# PowerandConnectors_2.net
KiCad netlist of a schematic drawn in Altium Designer
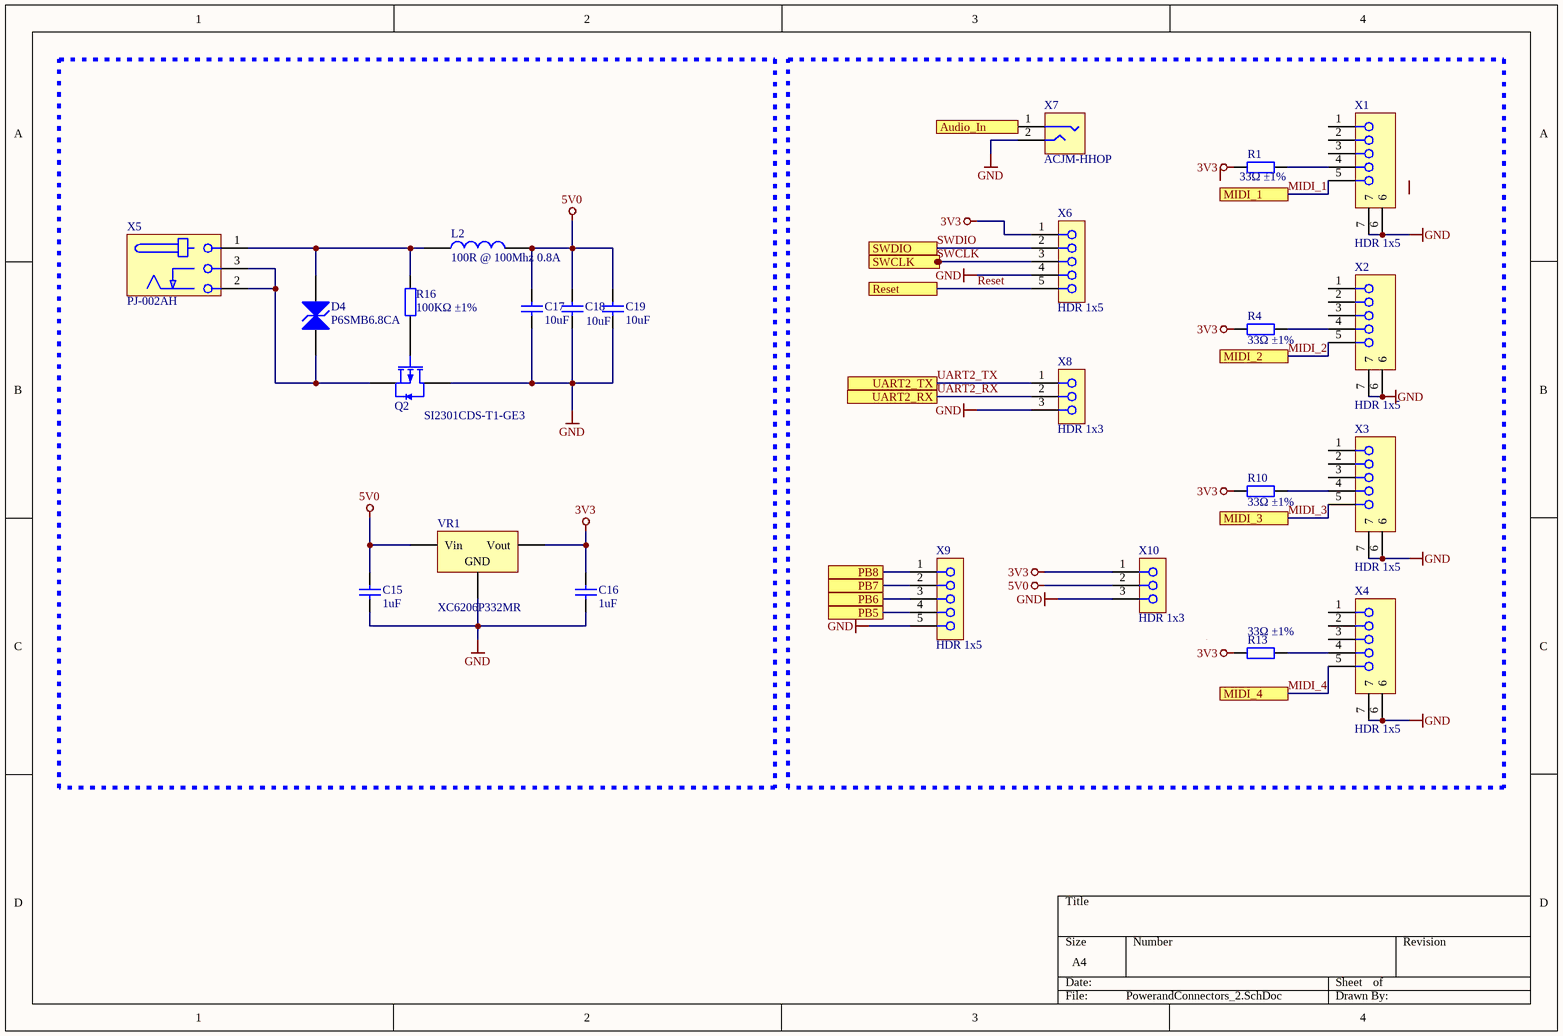
[diagram p0: PowerandConnectors_2.SchDoc]

(export (version "E")
  (design (tool "Eeschema 10.0.6"))
  (components
    (comp (ref "C15")
      (value "1uF")
      (footprint "0603_C")
      (description "Chip capacitors")
      (fields
        (field (name "MANUFACTURER") "Samsung Electro-Mechanics")
        (field (name "PARTNUMBER") "CL10A105KB8NNNC")
      )
      (libsource (lib "Cap") (part "0603 1uF (105) 10% 50V"))
    )
    (comp (ref "C16")
      (value "1uF")
      (footprint "0603_C")
      (description "Chip capacitors")
      (fields
        (field (name "MANUFACTURER") "Samsung Electro-Mechanics")
        (field (name "PARTNUMBER") "CL10A105KB8NNNC")
      )
      (libsource (lib "Cap") (part "0603 1uF (105) 10% 50V"))
    )
    (comp (ref "C17")
      (value "10uF")
      (footprint "0805_C")
      (description "Chip capacitors")
      (fields
        (field (name "MANUFACTURER") "Samsung Electro-Mechanics")
        (field (name "PARTNUMBER") "CL21A106KAYNNNE")
      )
      (libsource (lib "Cap") (part "0805 10uF (106) 10% 25V"))
    )
    (comp (ref "C18")
      (value "10uF")
      (footprint "0805_C")
      (description "Chip capacitors")
      (fields
        (field (name "MANUFACTURER") "Samsung Electro-Mechanics")
        (field (name "PARTNUMBER") "CL21A106KAYNNNE")
      )
      (libsource (lib "Cap") (part "0805 10uF (106) 10% 25V"))
    )
    (comp (ref "C19")
      (value "10uF")
      (footprint "0805_C")
      (description "Chip capacitors")
      (fields
        (field (name "MANUFACTURER") "Samsung Electro-Mechanics")
        (field (name "PARTNUMBER") "CL21A106KAYNNNE")
      )
      (libsource (lib "Cap") (part "0805 10uF (106) 10% 25V"))
    )
    (comp (ref "D4")
      (value "P6SMB6.8CA")
      (footprint "SMB(DO-214AA)_S1")
      (description "TVS")
      (libsource (lib "Diode") (part "SMB/DO-214AA P6SMB6.8CA"))
    )
    (comp (ref "L2")
      (value "100R @ 100Mhz 0.8A")
      (footprint "Miscellaneous Devices:6-0805_L")
      (description "Ferrite Bead")
      (libsource (lib "FBEAD") (part "0805 100R@100Mhz 0.8A"))
    )
    (comp (ref "Q2")
      (value "SI2301CDS-T1-GE3")
      (footprint "SOT-23(SOT-23-3)")
      (description "MOS(场效应管)")
      (libsource (lib "MOS") (part "SI2301CDS-T1-GE3"))
    )
    (comp (ref "R1")
      (value "33Ω ±1%")
      (footprint "0603_R")
      (description "Chip resistor")
      (fields (field (name "MANUFACTURER") "Uniroyal Elec") (field (name "PARTNUMBER") "0603WAF330JT5E"))
      (libsource (lib "RES") (part "0603 33R (33R0) 1%"))
    )
    (comp (ref "R4")
      (value "33Ω ±1%")
      (footprint "0603_R")
      (description "Chip resistor")
      (fields (field (name "MANUFACTURER") "Uniroyal Elec") (field (name "PARTNUMBER") "0603WAF330JT5E"))
      (libsource (lib "RES") (part "0603 33R (33R0) 1%"))
    )
    (comp (ref "R10")
      (value "33Ω ±1%")
      (footprint "0603_R")
      (description "Chip resistor")
      (fields (field (name "MANUFACTURER") "Uniroyal Elec") (field (name "PARTNUMBER") "0603WAF330JT5E"))
      (libsource (lib "RES") (part "0603 33R (33R0) 1%"))
    )
    (comp (ref "R13")
      (value "33Ω ±1%")
      (footprint "0603_R")
      (description "Chip resistor")
      (fields (field (name "MANUFACTURER") "Uniroyal Elec") (field (name "PARTNUMBER") "0603WAF330JT5E"))
      (libsource (lib "RES") (part "0603 33R (33R0) 1%"))
    )
    (comp (ref "R16")
      (value "100KΩ ±1%")
      (footprint "0603_R")
      (description "Chip resistor")
      (fields (field (name "MANUFACTURER") "Uniroyal Elec") (field (name "PARTNUMBER") "0603WAF1003T5E"))
      (libsource (lib "RES") (part "0603 100K (1003) 1%"))
    )
    (comp (ref "VR1")
      (value "XC6206P332MR")
      (footprint "SOT-23-3L")
      (description "低压差线性稳压(LDO)")
      (libsource (lib "LDO") (part "SOT-23 XC6206P332MR"))
    )
    (comp (ref "X1")
      (value "HDR 1x5")
      (footprint "MABP 5S")
      (description "Board-to-Board-Steckverbinder, 2.54 mm, 5 Kontakt(e), Stiftleiste 1-Reihig")
      (fields (field (name "MANUFACTURER") "BKL") (field (name "MANUFACTURER PART NUMBER") "MABP 5S"))
      (libsource (lib "Connectors") (part "CON_HEADER_1X5"))
    )
    (comp (ref "X2")
      (value "HDR 1x5")
      (footprint "MABP 5S")
      (description "Board-to-Board-Steckverbinder, 2.54 mm, 5 Kontakt(e), Stiftleiste 1-Reihig")
      (fields (field (name "MANUFACTURER") "BKL") (field (name "MANUFACTURER PART NUMBER") "MABP 5S"))
      (libsource (lib "Connectors") (part "CON_HEADER_1X5"))
    )
    (comp (ref "X3")
      (value "HDR 1x5")
      (footprint "MABP 5S")
      (description "Board-to-Board-Steckverbinder, 2.54 mm, 5 Kontakt(e), Stiftleiste 1-Reihig")
      (fields (field (name "MANUFACTURER") "BKL") (field (name "MANUFACTURER PART NUMBER") "MABP 5S"))
      (libsource (lib "Connectors") (part "CON_HEADER_1X5"))
    )
    (comp (ref "X4")
      (value "HDR 1x5")
      (footprint "MABP 5S")
      (description "Board-to-Board-Steckverbinder, 2.54 mm, 5 Kontakt(e), Stiftleiste 1-Reihig")
      (fields (field (name "MANUFACTURER") "BKL") (field (name "MANUFACTURER PART NUMBER") "MABP 5S"))
      (libsource (lib "Connectors") (part "CON_HEADER_1X5"))
    )
    (comp (ref "X5")
      (value "PJ-002AH")
      (footprint "PJ3L1400H110")
      (description "DC Power Connectors Power Jacks, Inside Contact Diameter 2mm, Outside Contact Diameter 6,5mm")
      (fields
        (field (name "MANUFACTURER") "CUI Devices")
        (field (name "LUMIRA PART NUMBER") "S-QMS-SPEC-32532")
      )
      (libsource (lib "_CONNECTORS") (part "PJ-002AH"))
    )
    (comp (ref "X6")
      (value "HDR 1x5")
      (footprint "CON_HEADER2.54_1x5W")
      (description "Board-to-Board-Steckverbinder, 2.54 mm, 5 Kontakt(e), Stiftleiste 1-Reihig")
      (fields
        (field (name "MANUFACTURER") "Samtec")
        (field (name "MANUFACTURER PART NUMBER") "TSW-105-07-T-S")
      )
      (libsource (lib "_CONNECTORS") (part "CON_HEADER_1X5"))
    )
    (comp (ref "X7")
      (value "ACJM-HHOP")
      (footprint "CUI_SJ-63072J")
      (description "Telefon-Steckverbinder 1/4\"JACK HOR CHASIS CON PLSTC MNT")
      (fields
        (field (name "MANUFACTURER") "CUI Devices")
        (field (name "MANUFACTURER PART NUMBER") "SJ-63072J")
      )
      (libsource (lib "Connectors") (part "Phone_Jack_1/4"))
    )
    (comp (ref "X8")
      (value "HDR 1x3")
      (footprint "CON_HEADER2.54_1x3W")
      (description "Board-to-Board-Steckverbinder, 2.54 mm, 3 Kontakt(e), Stiftleiste 1-Reihig")
      (fields
        (field (name "MANUFACTURER") "Samtec")
        (field (name "MANUFACTURER PART NUMBER") "TSW-103-07-T-S")
      )
      (libsource (lib "_CONNECTORS") (part "CON_HEADER_1X3"))
    )
    (comp (ref "X9")
      (value "HDR 1x5")
      (footprint "CON_HEADER2.54_1x5W")
      (description "Board-to-Board-Steckverbinder, 2.54 mm, 5 Kontakt(e), Stiftleiste 1-Reihig")
      (fields
        (field (name "MANUFACTURER") "Samtec")
        (field (name "MANUFACTURER PART NUMBER") "TSW-105-07-T-S")
      )
      (libsource (lib "_CONNECTORS") (part "CON_HEADER_1X5"))
    )
    (comp (ref "X10")
      (value "HDR 1x3")
      (footprint "CON_HEADER2.54_1x3W")
      (description "Board-to-Board-Steckverbinder, 2.54 mm, 3 Kontakt(e), Stiftleiste 1-Reihig")
      (fields
        (field (name "MANUFACTURER") "Samtec")
        (field (name "MANUFACTURER PART NUMBER") "TSW-103-07-T-S")
      )
      (libsource (lib "_CONNECTORS") (part "CON_HEADER_1X3"))
    )
  )
  (nets
    (net (code "1") (name "/Audio_In") (class "Default")
      (node (ref "X7") (pin "1") (pinfunction "1_1") (pintype "passive"))
    )
    (net (code "2") (name "/MIDI_1") (class "Default")
      (node (ref "X1") (pin "5") (pinfunction "5_5") (pintype "passive"))
    )
    (net (code "3") (name "/MIDI_2") (class "Default")
      (node (ref "X2") (pin "5") (pinfunction "5_5") (pintype "passive"))
    )
    (net (code "4") (name "/MIDI_3") (class "Default")
      (node (ref "X3") (pin "5") (pinfunction "5_5") (pintype "passive"))
    )
    (net (code "5") (name "/MIDI_4") (class "Default")
      (node (ref "X4") (pin "5") (pinfunction "5_5") (pintype "passive"))
    )
    (net (code "6") (name "/PB5") (class "Default")
      (node (ref "X9") (pin "4") (pinfunction "4_4") (pintype "passive"))
    )
    (net (code "7") (name "/PB6") (class "Default")
      (node (ref "X9") (pin "3") (pinfunction "3_3") (pintype "passive"))
    )
    (net (code "8") (name "/PB7") (class "Default")
      (node (ref "X9") (pin "2") (pinfunction "2_2") (pintype "passive"))
    )
    (net (code "9") (name "/PB8") (class "Default")
      (node (ref "X9") (pin "1") (pinfunction "1_1") (pintype "passive"))
    )
    (net (code "10") (name "/Reset") (class "Default")
      (node (ref "X6") (pin "5") (pinfunction "5_5") (pintype "passive"))
    )
    (net (code "11") (name "/SWCLK") (class "Default")
      (node (ref "X6") (pin "3") (pinfunction "3_3") (pintype "passive"))
    )
    (net (code "12") (name "/SWDIO") (class "Default")
      (node (ref "X6") (pin "2") (pinfunction "2_2") (pintype "passive"))
    )
    (net (code "13") (name "/UART2_RX") (class "Default")
      (node (ref "X8") (pin "2") (pinfunction "2_2") (pintype "passive"))
    )
    (net (code "14") (name "/UART2_TX") (class "Default")
      (node (ref "X8") (pin "1") (pinfunction "1_1") (pintype "passive"))
    )
    (net (code "15") (name "3V3") (class "Default")
      (node (ref "C16") (pin "2") (pinfunction "2_2") (pintype "passive"))
      (node (ref "R1") (pin "1") (pinfunction "1_1") (pintype "passive"))
      (node (ref "R10") (pin "1") (pinfunction "1_1") (pintype "passive"))
      (node (ref "R13") (pin "1") (pinfunction "1_1") (pintype "passive"))
      (node (ref "R4") (pin "1") (pinfunction "1_1") (pintype "passive"))
      (node (ref "VR1") (pin "2") (pinfunction "Vout_2") (pintype "passive"))
      (node (ref "X10") (pin "1") (pinfunction "1_1") (pintype "passive"))
      (node (ref "X6") (pin "1") (pinfunction "1_1") (pintype "passive"))
    )
    (net (code "16") (name "5V0") (class "Default")
      (node (ref "C15") (pin "2") (pinfunction "2_2") (pintype "passive"))
      (node (ref "C17") (pin "2") (pinfunction "2_2") (pintype "passive"))
      (node (ref "C18") (pin "2") (pinfunction "2_2") (pintype "passive"))
      (node (ref "C19") (pin "2") (pinfunction "2_2") (pintype "passive"))
      (node (ref "L2") (pin "2") (pinfunction "2_2") (pintype "passive"))
      (node (ref "VR1") (pin "3") (pinfunction "Vin_3") (pintype "passive"))
      (node (ref "X10") (pin "2") (pinfunction "2_2") (pintype "passive"))
    )
    (net (code "17") (name "GND") (class "Default")
      (node (ref "C15") (pin "1") (pinfunction "1_1") (pintype "passive"))
      (node (ref "C16") (pin "1") (pinfunction "1_1") (pintype "passive"))
      (node (ref "C17") (pin "1") (pinfunction "1_1") (pintype "passive"))
      (node (ref "C18") (pin "1") (pinfunction "1_1") (pintype "passive"))
      (node (ref "C19") (pin "1") (pinfunction "1_1") (pintype "passive"))
      (node (ref "Q2") (pin "3") (pinfunction "D_3") (pintype "passive"))
      (node (ref "VR1") (pin "1") (pinfunction "GND_1") (pintype "passive"))
      (node (ref "X1") (pin "6") (pinfunction "6_6") (pintype "passive"))
      (node (ref "X1") (pin "7") (pinfunction "7_7") (pintype "passive"))
      (node (ref "X10") (pin "3") (pinfunction "3_3") (pintype "passive"))
      (node (ref "X2") (pin "6") (pinfunction "6_6") (pintype "passive"))
      (node (ref "X2") (pin "7") (pinfunction "7_7") (pintype "passive"))
      (node (ref "X3") (pin "6") (pinfunction "6_6") (pintype "passive"))
      (node (ref "X3") (pin "7") (pinfunction "7_7") (pintype "passive"))
      (node (ref "X4") (pin "6") (pinfunction "6_6") (pintype "passive"))
      (node (ref "X4") (pin "7") (pinfunction "7_7") (pintype "passive"))
      (node (ref "X6") (pin "4") (pinfunction "4_4") (pintype "passive"))
      (node (ref "X7") (pin "2") (pinfunction "2_2") (pintype "passive"))
      (node (ref "X8") (pin "3") (pinfunction "3_3") (pintype "passive"))
      (node (ref "X9") (pin "5") (pinfunction "5_5") (pintype "passive"))
    )
    (net (code "18") (name "Net-(D4-A)") (class "Default")
      (node (ref "D4") (pin "1") (pinfunction "A_1") (pintype "passive"))
      (node (ref "Q2") (pin "2") (pinfunction "S_2") (pintype "passive"))
      (node (ref "X5") (pin "2") (pinfunction "2_2") (pintype "passive"))
      (node (ref "X5") (pin "3") (pinfunction "3_3") (pintype "passive"))
    )
    (net (code "19") (name "Net-(D4-K)") (class "Default")
      (node (ref "D4") (pin "2") (pinfunction "K_2") (pintype "passive"))
      (node (ref "L2") (pin "1") (pinfunction "1_1") (pintype "passive"))
      (node (ref "R16") (pin "2") (pinfunction "2_2") (pintype "passive"))
      (node (ref "X5") (pin "1") (pinfunction "1_1") (pintype "passive"))
    )
    (net (code "20") (name "Net-(Q2-G)") (class "Default")
      (node (ref "Q2") (pin "1") (pinfunction "G_1") (pintype "passive"))
      (node (ref "R16") (pin "1") (pinfunction "1_1") (pintype "passive"))
    )
    (net (code "21") (name "Net-(R1-Pad2)") (class "Default")
      (node (ref "R1") (pin "2") (pinfunction "2_2") (pintype "passive"))
      (node (ref "X1") (pin "4") (pinfunction "4_4") (pintype "passive"))
    )
    (net (code "22") (name "Net-(R4-Pad2)") (class "Default")
      (node (ref "R4") (pin "2") (pinfunction "2_2") (pintype "passive"))
      (node (ref "X2") (pin "4") (pinfunction "4_4") (pintype "passive"))
    )
    (net (code "23") (name "Net-(R10-Pad2)") (class "Default")
      (node (ref "R10") (pin "2") (pinfunction "2_2") (pintype "passive"))
      (node (ref "X3") (pin "4") (pinfunction "4_4") (pintype "passive"))
    )
    (net (code "24") (name "Net-(R13-Pad2)") (class "Default")
      (node (ref "R13") (pin "2") (pinfunction "2_2") (pintype "passive"))
      (node (ref "X4") (pin "4") (pinfunction "4_4") (pintype "passive"))
    )
    (net (code "25") (name "unconnected-(X1-Pad1)") (class "Default")
      (node (ref "X1") (pin "1") (pinfunction "1_1") (pintype "passive"))
    )
    (net (code "26") (name "unconnected-(X1-Pad2)") (class "Default")
      (node (ref "X1") (pin "2") (pinfunction "2_2") (pintype "passive"))
    )
    (net (code "27") (name "unconnected-(X1-Pad3)") (class "Default")
      (node (ref "X1") (pin "3") (pinfunction "3_3") (pintype "passive"))
    )
    (net (code "28") (name "unconnected-(X2-Pad1)") (class "Default")
      (node (ref "X2") (pin "1") (pinfunction "1_1") (pintype "passive"))
    )
    (net (code "29") (name "unconnected-(X2-Pad2)") (class "Default")
      (node (ref "X2") (pin "2") (pinfunction "2_2") (pintype "passive"))
    )
    (net (code "30") (name "unconnected-(X2-Pad3)") (class "Default")
      (node (ref "X2") (pin "3") (pinfunction "3_3") (pintype "passive"))
    )
    (net (code "31") (name "unconnected-(X3-Pad1)") (class "Default")
      (node (ref "X3") (pin "1") (pinfunction "1_1") (pintype "passive"))
    )
    (net (code "32") (name "unconnected-(X3-Pad2)") (class "Default")
      (node (ref "X3") (pin "2") (pinfunction "2_2") (pintype "passive"))
    )
    (net (code "33") (name "unconnected-(X3-Pad3)") (class "Default")
      (node (ref "X3") (pin "3") (pinfunction "3_3") (pintype "passive"))
    )
    (net (code "34") (name "unconnected-(X4-Pad1)") (class "Default")
      (node (ref "X4") (pin "1") (pinfunction "1_1") (pintype "passive"))
    )
    (net (code "35") (name "unconnected-(X4-Pad2)") (class "Default")
      (node (ref "X4") (pin "2") (pinfunction "2_2") (pintype "passive"))
    )
    (net (code "36") (name "unconnected-(X4-Pad3)") (class "Default")
      (node (ref "X4") (pin "3") (pinfunction "3_3") (pintype "passive"))
    )
  )
)
